# schematic6.net
KiCad netlist of a schematic drawn in Altium Designer
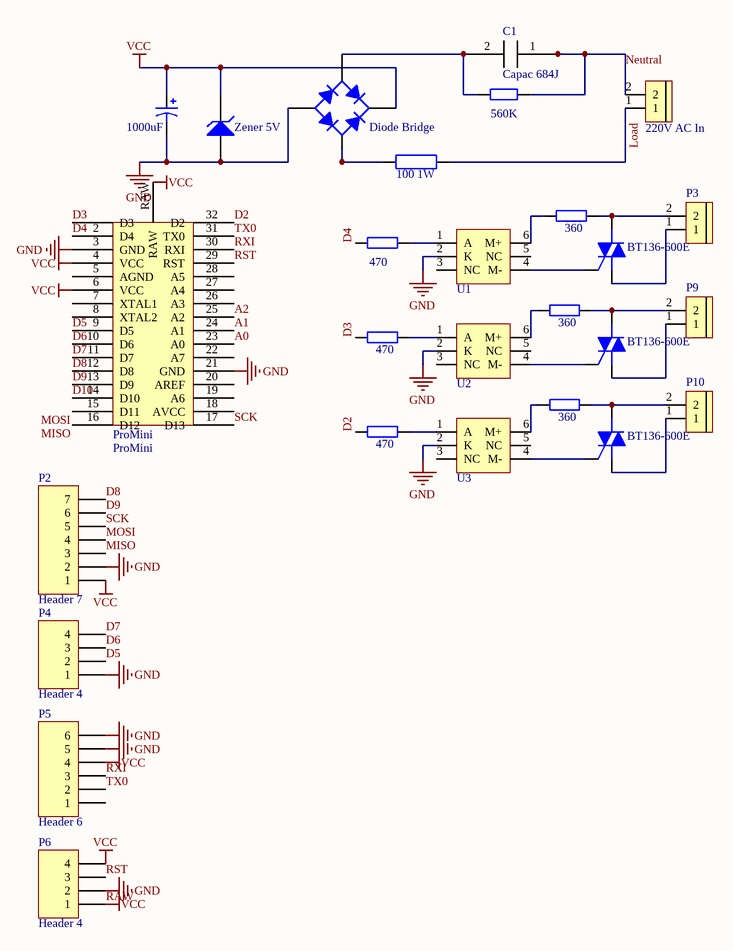
[diagram p0: schematic6.SchDoc]

(export (version "E")
  (design (tool "Eeschema 10.0.6"))
  (components
    (comp (ref "C1")
      (value "Capac 684J")
      (footprint "Tu keo 684J 400V")
      (libsource (lib "ArduinoLib") (part "Tu keo 684J 400V"))
    )
    (comp (ref "C3")
      (value "1000uF")
      (footprint "C10mm")
      (description "Polarized Capacitor (Axial)")
      (fields (field (name "PUBLISHER") "Altium Limited"))
      (libsource (lib "NBBLib 14-03-2012") (part "Cap Pol 8mm"))
    )
    (comp (ref "D1")
      (value "Diode Bridge")
      (footprint "D-38")
      (description "Full Wave Diode Bridge")
      (fields (field (name "PUBLISHER") "Altium Limited"))
      (libsource (lib "Miscellaneous Devices") (part "Bridge1"))
    )
    (comp (ref "D3")
      (value "Zener 5V")
      (footprint "DIODE/NOM/0.5A")
      (description "Zener Diode")
      (fields (field (name "VOLTAGE") "5") (field (name "PUBLISHER") "Altium Limited"))
      (libsource (lib "NBBLib 14-03-2012") (part "Diode Zener"))
    )
    (comp (ref "P1")
      (value "220V AC In")
      (footprint "BIG_Header 2")
      (libsource (lib "NBBLib 14-03-2012") (part "BIG_Header 2"))
    )
    (comp (ref "P2")
      (value "Header 7")
      (footprint "HDR1X7")
      (description "Header, 7-Pin")
      (fields (field (name "PUBLISHER") "Altium Limited"))
      (libsource (lib "NBBLib 14-03-2012") (part "Header 7"))
    )
    (comp (ref "P3")
      (value "BIG_Header 2")
      (footprint "BIG_Header 2")
      (libsource (lib "NBBLib 14-03-2012") (part "BIG_Header 2"))
    )
    (comp (ref "P4")
      (value "Header 4")
      (footprint "HDR1X4")
      (description "Header, 4-Pin")
      (fields (field (name "PUBLISHER") "Altium Limited"))
      (libsource (lib "Miscellaneous Connectors") (part "Header 4"))
    )
    (comp (ref "P5")
      (value "Header 6")
      (footprint "HDR1X6")
      (description "Header, 6-Pin")
      (fields (field (name "PUBLISHER") "Altium Limited"))
      (libsource (lib "Miscellaneous Connectors") (part "Header 6"))
    )
    (comp (ref "P6")
      (value "Header 4")
      (footprint "HDR1X4")
      (description "Header, 4-Pin")
      (fields (field (name "PUBLISHER") "Altium Limited"))
      (libsource (lib "Miscellaneous Connectors") (part "Header 4"))
    )
    (comp (ref "P9")
      (value "BIG_Header 2")
      (footprint "BIG_Header 2")
      (libsource (lib "NBBLib 14-03-2012") (part "BIG_Header 2"))
    )
    (comp (ref "P10")
      (value "BIG_Header 2")
      (footprint "BIG_Header 2")
      (libsource (lib "NBBLib 14-03-2012") (part "BIG_Header 2"))
    )
    (comp (ref "ProMini")
      (value "ProMini")
      (footprint "Arduino Pro Mini")
      (libsource (lib "ArduinoLib") (part "Pro Mini"))
    )
    (comp (ref "Q1")
      (value "BT136-600E")
      (footprint "BTA6-600")
      (description "Silicon Bidirectional Triode Thyristor")
      (fields (field (name "PUBLISHER") "Altium Limited"))
      (libsource (lib "NBBLib 14-03-2012") (part "BTA12-600"))
    )
    (comp (ref "Q2")
      (value "BT136-600E")
      (footprint "BTA6-600")
      (description "Silicon Bidirectional Triode Thyristor")
      (fields (field (name "PUBLISHER") "Altium Limited"))
      (libsource (lib "NBBLib 14-03-2012") (part "BTA12-600"))
    )
    (comp (ref "Q3")
      (value "BT136-600E")
      (footprint "BTA6-600")
      (description "Silicon Bidirectional Triode Thyristor")
      (fields (field (name "PUBLISHER") "Altium Limited"))
      (libsource (lib "NBBLib 14-03-2012") (part "BTA12-600"))
    )
    (comp (ref "R1")
      (value "100 1W")
      (footprint "DIEN TRO 1W (tube)")
      (description "1W Res Power")
      (fields (field (name "VOLTAGE") "400") (field (name "CREATOR") "Nguyen Ba Bien"))
      (libsource (lib "NBBLib 14-03-2012") (part "Res 1W"))
    )
    (comp (ref "R3")
      (value "560K")
      (footprint "AXIAL-0.4")
      (description "Resistor")
      (fields (field (name "PUBLISHER") "Altium Limited"))
      (libsource (lib "Miscellaneous Devices") (part "Res2"))
    )
    (comp (ref "R4")
      (value "470")
      (footprint "R1/4W")
      (description "Resistor")
      (libsource (lib "t.thien") (part "R1/4W"))
    )
    (comp (ref "R5")
      (value "360")
      (footprint "R1/4W")
      (description "Resistor")
      (libsource (lib "t.thien") (part "R1/4W"))
    )
    (comp (ref "R7")
      (value "470")
      (footprint "R1/4W")
      (description "Resistor")
      (libsource (lib "t.thien") (part "R1/4W"))
    )
    (comp (ref "R8")
      (value "360")
      (footprint "R1/4W")
      (description "Resistor")
      (libsource (lib "t.thien") (part "R1/4W"))
    )
    (comp (ref "R9")
      (value "470")
      (footprint "R1/4W")
      (description "Resistor")
      (libsource (lib "t.thien") (part "R1/4W"))
    )
    (comp (ref "R10")
      (value "360")
      (footprint "R1/4W")
      (description "Resistor")
      (libsource (lib "t.thien") (part "R1/4W"))
    )
    (comp (ref "U1")
      (value "MOC3021M")
      (footprint "MOC30XX")
      (libsource (lib "NBBLib 14-03-2012") (part "MOC3021M"))
    )
    (comp (ref "U2")
      (value "MOC3021M")
      (footprint "MOC30XX")
      (libsource (lib "NBBLib 14-03-2012") (part "MOC3021M"))
    )
    (comp (ref "U3")
      (value "MOC3021M")
      (footprint "MOC30XX")
      (libsource (lib "NBBLib 14-03-2012") (part "MOC3021M"))
    )
  )
  (nets
    (net (code "1") (name "/A0") (class "Default")
      (node (ref "ProMini") (pin "23") (pinfunction "A0_23") (pintype "passive"))
    )
    (net (code "2") (name "/A1") (class "Default")
      (node (ref "ProMini") (pin "24") (pinfunction "A1_24") (pintype "passive"))
    )
    (net (code "3") (name "/A2") (class "Default")
      (node (ref "ProMini") (pin "25") (pinfunction "A2_25") (pintype "passive"))
    )
    (net (code "4") (name "/D2") (class "Default")
      (node (ref "ProMini") (pin "32") (pinfunction "D2_32") (pintype "passive"))
      (node (ref "R9") (pin "1") (pinfunction "1_1") (pintype "passive"))
    )
    (net (code "5") (name "/D3") (class "Default")
      (node (ref "ProMini") (pin "1") (pinfunction "D3_1") (pintype "passive"))
      (node (ref "R7") (pin "1") (pinfunction "1_1") (pintype "passive"))
    )
    (net (code "6") (name "/D4") (class "Default")
      (node (ref "ProMini") (pin "2") (pinfunction "D4_2") (pintype "passive"))
      (node (ref "R4") (pin "1") (pinfunction "1_1") (pintype "passive"))
    )
    (net (code "7") (name "/D5") (class "Default")
      (node (ref "P4") (pin "2") (pinfunction "2_2") (pintype "passive"))
      (node (ref "ProMini") (pin "9") (pinfunction "D5_9") (pintype "passive"))
    )
    (net (code "8") (name "/D6") (class "Default")
      (node (ref "P4") (pin "3") (pinfunction "3_3") (pintype "passive"))
      (node (ref "ProMini") (pin "10") (pinfunction "D6_10") (pintype "passive"))
    )
    (net (code "9") (name "/D7") (class "Default")
      (node (ref "P4") (pin "4") (pinfunction "4_4") (pintype "passive"))
      (node (ref "ProMini") (pin "11") (pinfunction "D7_11") (pintype "passive"))
    )
    (net (code "10") (name "/D8") (class "Default")
      (node (ref "P2") (pin "7") (pinfunction "7_7") (pintype "passive"))
      (node (ref "ProMini") (pin "12") (pinfunction "D8_12") (pintype "passive"))
    )
    (net (code "11") (name "/D9") (class "Default")
      (node (ref "P2") (pin "6") (pinfunction "6_6") (pintype "passive"))
      (node (ref "ProMini") (pin "13") (pinfunction "D9_13") (pintype "passive"))
    )
    (net (code "12") (name "/D10") (class "Default")
      (node (ref "ProMini") (pin "14") (pinfunction "D10_14") (pintype "passive"))
    )
    (net (code "13") (name "/Load") (class "Default")
      (node (ref "P1") (pin "1") (pinfunction "1_1") (pintype "passive"))
      (node (ref "R1") (pin "2") (pinfunction "2_2") (pintype "passive"))
    )
    (net (code "14") (name "/MISO") (class "Default")
      (node (ref "P2") (pin "3") (pinfunction "3_3") (pintype "passive"))
      (node (ref "ProMini") (pin "16") (pinfunction "D12_16") (pintype "passive"))
    )
    (net (code "15") (name "/MOSI") (class "Default")
      (node (ref "P2") (pin "4") (pinfunction "4_4") (pintype "passive"))
      (node (ref "ProMini") (pin "15") (pinfunction "D11_15") (pintype "passive"))
    )
    (net (code "16") (name "/Neutral") (class "Default")
      (node (ref "C1") (pin "1") (pinfunction "1_1") (pintype "passive"))
      (node (ref "P1") (pin "2") (pinfunction "2_2") (pintype "passive"))
      (node (ref "R3") (pin "2") (pinfunction "2_2") (pintype "passive"))
    )
    (net (code "17") (name "/RST") (class "Default")
      (node (ref "P6") (pin "3") (pinfunction "3_3") (pintype "passive"))
      (node (ref "ProMini") (pin "29") (pinfunction "RST_29") (pintype "passive"))
    )
    (net (code "18") (name "/RXI") (class "Default")
      (node (ref "P5") (pin "3") (pinfunction "3_3") (pintype "passive"))
      (node (ref "ProMini") (pin "30") (pinfunction "RXI_30") (pintype "passive"))
    )
    (net (code "19") (name "/SCK") (class "Default")
      (node (ref "P2") (pin "5") (pinfunction "5_5") (pintype "passive"))
      (node (ref "ProMini") (pin "17") (pinfunction "D13_17") (pintype "passive"))
    )
    (net (code "20") (name "/TX0") (class "Default")
      (node (ref "P5") (pin "2") (pinfunction "2_2") (pintype "passive"))
      (node (ref "ProMini") (pin "31") (pinfunction "TX0_31") (pintype "passive"))
    )
    (net (code "21") (name "GND") (class "Default")
      (node (ref "C3") (pin "2") (pinfunction "2_2") (pintype "passive"))
      (node (ref "D1") (pin "3") (pinfunction "A_3") (pintype "passive"))
      (node (ref "D3") (pin "1") (pinfunction "A_1") (pintype "passive"))
      (node (ref "P2") (pin "2") (pinfunction "2_2") (pintype "passive"))
      (node (ref "P4") (pin "1") (pinfunction "1_1") (pintype "passive"))
      (node (ref "P5") (pin "5") (pinfunction "5_5") (pintype "passive"))
      (node (ref "P5") (pin "6") (pinfunction "6_6") (pintype "passive"))
      (node (ref "P6") (pin "2") (pinfunction "2_2") (pintype "passive"))
      (node (ref "ProMini") (pin "21") (pinfunction "GND_21") (pintype "passive"))
      (node (ref "ProMini") (pin "3") (pinfunction "GND_3") (pintype "passive"))
      (node (ref "U1") (pin "2") (pinfunction "K_2") (pintype "passive"))
      (node (ref "U2") (pin "2") (pinfunction "K_2") (pintype "passive"))
      (node (ref "U3") (pin "2") (pinfunction "K_2") (pintype "passive"))
    )
    (net (code "22") (name "Net-(C1-Pad2)") (class "Default")
      (node (ref "C1") (pin "2") (pinfunction "2_2") (pintype "passive"))
      (node (ref "D1") (pin "4") (pinfunction "C_4") (pintype "passive"))
      (node (ref "R3") (pin "1") (pinfunction "1_1") (pintype "passive"))
    )
    (net (code "23") (name "Net-(D1-C-Pad2)") (class "Default")
      (node (ref "D1") (pin "2") (pinfunction "C_2") (pintype "passive"))
      (node (ref "R1") (pin "1") (pinfunction "1_1") (pintype "passive"))
    )
    (net (code "24") (name "Net-(Q1-G)") (class "Default")
      (node (ref "Q1") (pin "3") (pinfunction "G_3") (pintype "passive"))
      (node (ref "U1") (pin "4") (pinfunction "M-_4") (pintype "passive"))
    )
    (net (code "25") (name "Net-(Q1-M1)") (class "Default")
      (node (ref "P3") (pin "1") (pinfunction "1_1") (pintype "passive"))
      (node (ref "Q1") (pin "1") (pinfunction "M1_1") (pintype "passive"))
    )
    (net (code "26") (name "Net-(Q1-M2)") (class "Default")
      (node (ref "P3") (pin "2") (pinfunction "2_2") (pintype "passive"))
      (node (ref "Q1") (pin "2") (pinfunction "M2_2") (pintype "passive"))
      (node (ref "R5") (pin "2") (pinfunction "2_2") (pintype "passive"))
    )
    (net (code "27") (name "Net-(Q2-G)") (class "Default")
      (node (ref "Q2") (pin "3") (pinfunction "G_3") (pintype "passive"))
      (node (ref "U2") (pin "4") (pinfunction "M-_4") (pintype "passive"))
    )
    (net (code "28") (name "Net-(Q2-M1)") (class "Default")
      (node (ref "P9") (pin "1") (pinfunction "1_1") (pintype "passive"))
      (node (ref "Q2") (pin "1") (pinfunction "M1_1") (pintype "passive"))
    )
    (net (code "29") (name "Net-(Q2-M2)") (class "Default")
      (node (ref "P9") (pin "2") (pinfunction "2_2") (pintype "passive"))
      (node (ref "Q2") (pin "2") (pinfunction "M2_2") (pintype "passive"))
      (node (ref "R8") (pin "2") (pinfunction "2_2") (pintype "passive"))
    )
    (net (code "30") (name "Net-(Q3-G)") (class "Default")
      (node (ref "Q3") (pin "3") (pinfunction "G_3") (pintype "passive"))
      (node (ref "U3") (pin "4") (pinfunction "M-_4") (pintype "passive"))
    )
    (net (code "31") (name "Net-(Q3-M1)") (class "Default")
      (node (ref "P10") (pin "1") (pinfunction "1_1") (pintype "passive"))
      (node (ref "Q3") (pin "1") (pinfunction "M1_1") (pintype "passive"))
    )
    (net (code "32") (name "Net-(Q3-M2)") (class "Default")
      (node (ref "P10") (pin "2") (pinfunction "2_2") (pintype "passive"))
      (node (ref "Q3") (pin "2") (pinfunction "M2_2") (pintype "passive"))
      (node (ref "R10") (pin "2") (pinfunction "2_2") (pintype "passive"))
    )
    (net (code "33") (name "Net-(U1-A)") (class "Default")
      (node (ref "R4") (pin "2") (pinfunction "2_2") (pintype "passive"))
      (node (ref "U1") (pin "1") (pinfunction "A_1") (pintype "passive"))
    )
    (net (code "34") (name "Net-(U1-M+)") (class "Default")
      (node (ref "R5") (pin "1") (pinfunction "1_1") (pintype "passive"))
      (node (ref "U1") (pin "6") (pinfunction "M+_6") (pintype "passive"))
    )
    (net (code "35") (name "Net-(U2-A)") (class "Default")
      (node (ref "R7") (pin "2") (pinfunction "2_2") (pintype "passive"))
      (node (ref "U2") (pin "1") (pinfunction "A_1") (pintype "passive"))
    )
    (net (code "36") (name "Net-(U2-M+)") (class "Default")
      (node (ref "R8") (pin "1") (pinfunction "1_1") (pintype "passive"))
      (node (ref "U2") (pin "6") (pinfunction "M+_6") (pintype "passive"))
    )
    (net (code "37") (name "Net-(U3-A)") (class "Default")
      (node (ref "R9") (pin "2") (pinfunction "2_2") (pintype "passive"))
      (node (ref "U3") (pin "1") (pinfunction "A_1") (pintype "passive"))
    )
    (net (code "38") (name "Net-(U3-M+)") (class "Default")
      (node (ref "R10") (pin "1") (pinfunction "1_1") (pintype "passive"))
      (node (ref "U3") (pin "6") (pinfunction "M+_6") (pintype "passive"))
    )
    (net (code "39") (name "VCC") (class "Default")
      (node (ref "C3") (pin "1") (pinfunction "1_1") (pintype "passive"))
      (node (ref "D1") (pin "1") (pinfunction "K_1") (pintype "passive"))
      (node (ref "D3") (pin "2") (pinfunction "K_2") (pintype "passive"))
      (node (ref "P2") (pin "1") (pinfunction "1_1") (pintype "passive"))
      (node (ref "P5") (pin "4") (pinfunction "4_4") (pintype "passive"))
      (node (ref "P6") (pin "1") (pinfunction "1_1") (pintype "passive"))
      (node (ref "P6") (pin "4") (pinfunction "4_4") (pintype "passive"))
      (node (ref "ProMini") (pin "4") (pinfunction "VCC_4") (pintype "passive"))
      (node (ref "ProMini") (pin "6") (pinfunction "VCC_6") (pintype "passive"))
      (node (ref "ProMini") (pin "RAW") (pinfunction "RAW_RAW") (pintype "passive"))
    )
    (net (code "40") (name "unconnected-(P5-Pad1)") (class "Default")
      (node (ref "P5") (pin "1") (pinfunction "1_1") (pintype "passive"))
    )
    (net (code "41") (name "unconnected-(ProMini-A3-Pad26)") (class "Default")
      (node (ref "ProMini") (pin "26") (pinfunction "A3_26") (pintype "passive"))
    )
    (net (code "42") (name "unconnected-(ProMini-A4-Pad27)") (class "Default")
      (node (ref "ProMini") (pin "27") (pinfunction "A4_27") (pintype "passive"))
    )
    (net (code "43") (name "unconnected-(ProMini-A5-Pad28)") (class "Default")
      (node (ref "ProMini") (pin "28") (pinfunction "A5_28") (pintype "passive"))
    )
    (net (code "44") (name "unconnected-(ProMini-A6-Pad19)") (class "Default")
      (node (ref "ProMini") (pin "19") (pinfunction "A6_19") (pintype "passive"))
    )
    (net (code "45") (name "unconnected-(ProMini-A7-Pad22)") (class "Default")
      (node (ref "ProMini") (pin "22") (pinfunction "A7_22") (pintype "passive"))
    )
    (net (code "46") (name "unconnected-(ProMini-AGND-Pad5)") (class "Default")
      (node (ref "ProMini") (pin "5") (pinfunction "AGND_5") (pintype "passive"))
    )
    (net (code "47") (name "unconnected-(ProMini-AREF-Pad20)") (class "Default")
      (node (ref "ProMini") (pin "20") (pinfunction "AREF_20") (pintype "passive"))
    )
    (net (code "48") (name "unconnected-(ProMini-AVCC-Pad18)") (class "Default")
      (node (ref "ProMini") (pin "18") (pinfunction "AVCC_18") (pintype "passive"))
    )
    (net (code "49") (name "unconnected-(ProMini-XTAL1-Pad7)") (class "Default")
      (node (ref "ProMini") (pin "7") (pinfunction "XTAL1_7") (pintype "passive"))
    )
    (net (code "50") (name "unconnected-(ProMini-XTAL2-Pad8)") (class "Default")
      (node (ref "ProMini") (pin "8") (pinfunction "XTAL2_8") (pintype "passive"))
    )
    (net (code "51") (name "unconnected-(U1-NC-Pad3)") (class "Default")
      (node (ref "U1") (pin "3") (pinfunction "NC_3") (pintype "passive"))
    )
    (net (code "52") (name "unconnected-(U1-NC-Pad5)") (class "Default")
      (node (ref "U1") (pin "5") (pinfunction "NC_5") (pintype "passive"))
    )
    (net (code "53") (name "unconnected-(U2-NC-Pad3)") (class "Default")
      (node (ref "U2") (pin "3") (pinfunction "NC_3") (pintype "passive"))
    )
    (net (code "54") (name "unconnected-(U2-NC-Pad5)") (class "Default")
      (node (ref "U2") (pin "5") (pinfunction "NC_5") (pintype "passive"))
    )
    (net (code "55") (name "unconnected-(U3-NC-Pad3)") (class "Default")
      (node (ref "U3") (pin "3") (pinfunction "NC_3") (pintype "passive"))
    )
    (net (code "56") (name "unconnected-(U3-NC-Pad5)") (class "Default")
      (node (ref "U3") (pin "5") (pinfunction "NC_5") (pintype "passive"))
    )
  )
)
